# 10_Motor_Driver_2.net
KiCad netlist of a schematic drawn in Altium Designer
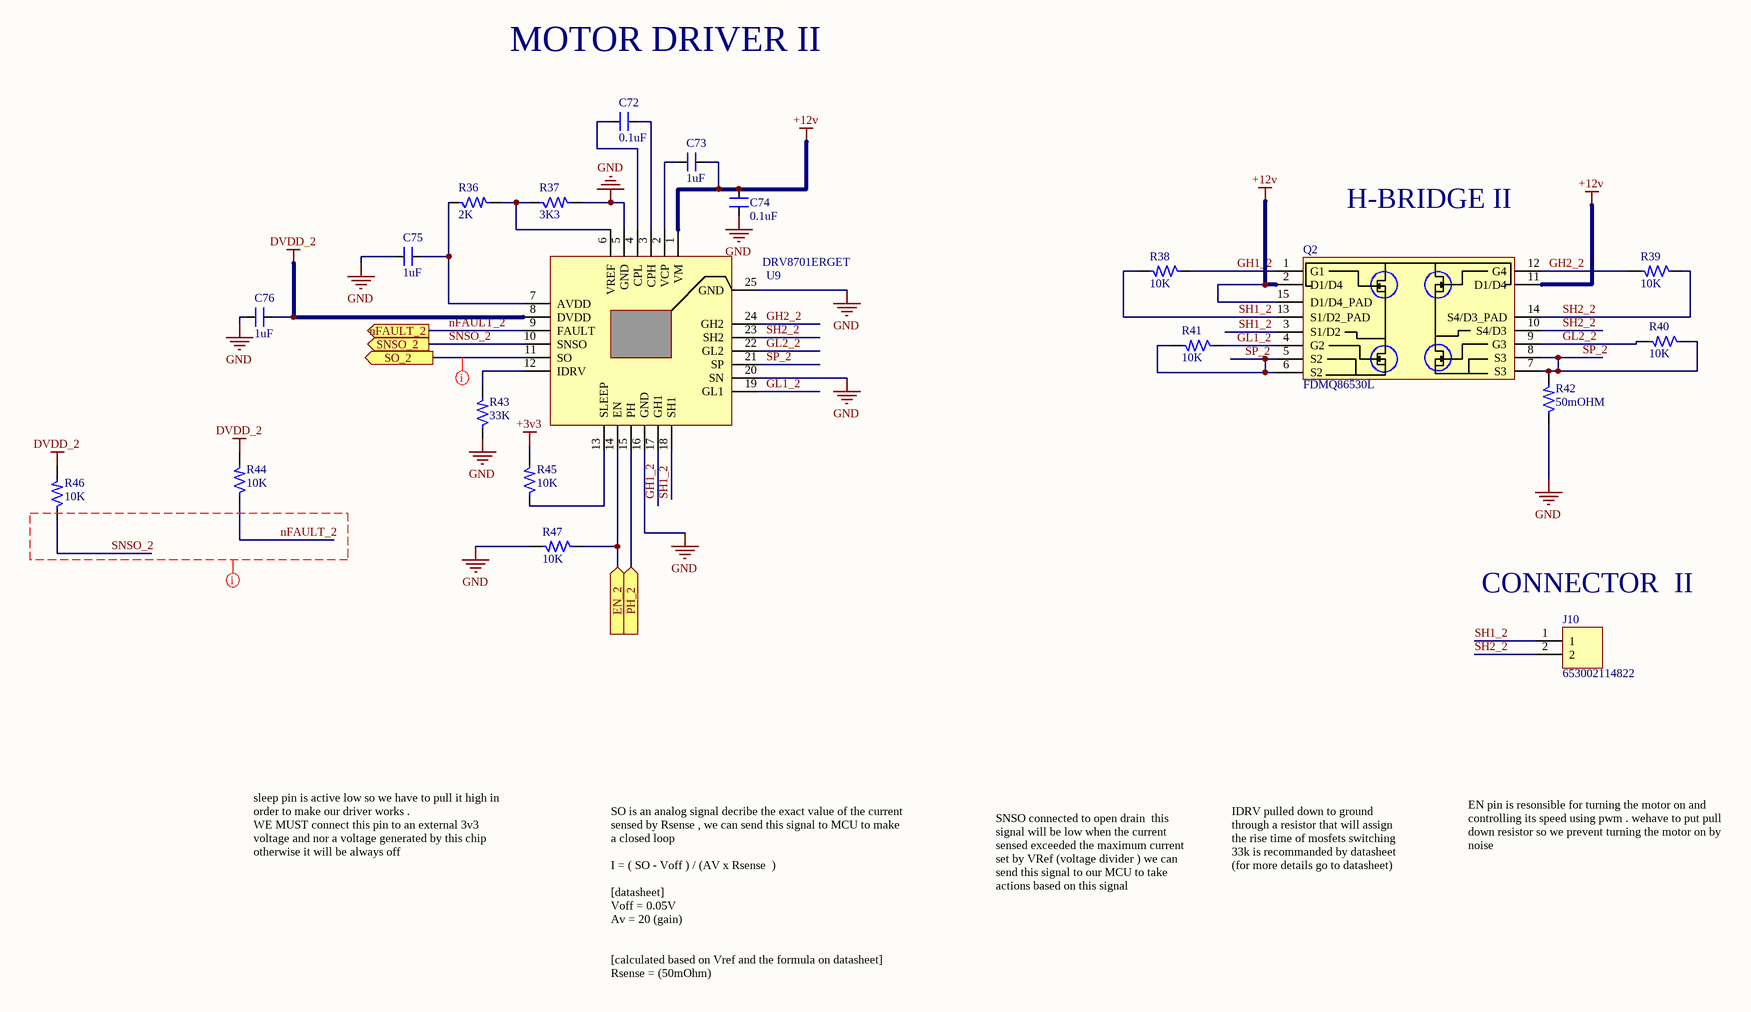
[diagram p0: [10]Motor_Driver_2.SchDoc]

(export (version "E")
  (design (tool "Eeschema 10.0.6"))
  (components
    (comp (ref "C72")
      (value "0.1uF")
      (footprint "CAP_0805")
      (description "0.1µF ±5% 50V Ceramic Capacitor X7R 0805 (2012 Metric)")
      (fields
        (field (name "MANUFACTURER") "AVX Corporation")
        (field (name "MANUFACTURER PART NUMBER") "08055C104JAT4A")
      )
      (libsource (lib "ESTEEMPCBLIB") (part "CAP_0.1uF-50V-5%-0805"))
    )
    (comp (ref "C73")
      (value "1uF")
      (footprint "CAP_0805")
      (description "1µF ±5% 50V Ceramic Capacitor X7R 0805 (2012 Metric)")
      (fields
        (field (name "MANUFACTURER") "Samsung")
        (field (name "MANUFACTURER PART NUMBER") "CC0805JKX7R9BB105")
      )
      (libsource (lib "ESTEEMPCBLIB") (part "CAP_1uF-50V-5%-0805"))
    )
    (comp (ref "C74")
      (value "0.1uF")
      (footprint "CAP_0805")
      (description "0.1µF ±5% 50V Ceramic Capacitor X7R 0805 (2012 Metric)")
      (fields
        (field (name "MANUFACTURER") "AVX Corporation")
        (field (name "MANUFACTURER PART NUMBER") "08055C104JAT4A")
      )
      (libsource (lib "ESTEEMPCBLIB") (part "CAP_0.1uF-50V-5%-0805"))
    )
    (comp (ref "C75")
      (value "1uF")
      (footprint "CAP_0805")
      (description "1µF ±5% 50V Ceramic Capacitor X7R 0805 (2012 Metric)")
      (fields
        (field (name "MANUFACTURER") "Samsung")
        (field (name "MANUFACTURER PART NUMBER") "CC0805JKX7R9BB105")
      )
      (libsource (lib "ESTEEMPCBLIB") (part "CAP_1uF-50V-5%-0805"))
    )
    (comp (ref "C76")
      (value "1uF")
      (footprint "CAP_0805")
      (description "1µF ±5% 50V Ceramic Capacitor X7R 0805 (2012 Metric)")
      (fields
        (field (name "MANUFACTURER") "Samsung")
        (field (name "MANUFACTURER PART NUMBER") "CC0805JKX7R9BB105")
      )
      (libsource (lib "ESTEEMPCBLIB") (part "CAP_1uF-50V-5%-0805"))
    )
    (comp (ref "J10")
      (value "653002114822")
      (footprint "CON2_50_653002114822_TH_ST")
      (description "2 Pins, 1 Row 1.25mm Pitch, Straight Connector, male")
      (fields (field (name "MANUFACTURER") "JST") (field (name "MATING PART NUMBER") "653002113322"))
      (libsource (lib "ESTEEMPCBLIB") (part "CON-PLG_2X1-50-ST-TH"))
    )
    (comp (ref "Q2")
      (value "FDMQ86530L")
      (footprint "DFN5045-12_33_212_27X15_SMD_1")
      (description "Mosfet Array 4 N-Channel 8A (Ta) Surface Mount V-DFN5045-12")
      (fields (field (name "MANUFACTURER") "ON Semiconductor"))
      (libsource (lib "ESTEEMPCBLIB") (part "MOSFET-N_60V-8A-V-DFN5045-12"))
    )
    (comp (ref "R36")
      (value "2K")
      (footprint "RES_0805")
      (description "2 kOhms ±1% 0.125W, 1/8W Chip Resistor 0805 (2012 Metric) Moisture Resistant Thick Film")
      (fields
        (field (name "MANUFACTURER") "TE Connectivity")
        (field (name "MANUFACTURER PART NUMBER") "RC0805FR-072KL")
      )
      (libsource (lib "ESTEEMPCBLIB") (part "RES_2K-0.125W-1%-0805"))
    )
    (comp (ref "R37")
      (value "3K3")
      (footprint "RES_0603")
      (description "3.3 kOhms ±1% 0.1W, 1/10W Chip Resistor 0603 (1608 Metric) Automotive AEC-Q200 Thick Film")
      (fields (field (name "MANUFACTURER") "Wilson") (field (name "MANUFACTURER PART NUMBER") "WR06X3301FTL"))
      (libsource (lib "ESTEEMPCBLIB") (part "RES_3.3K-0.1W-1%-0603"))
    )
    (comp (ref "R38")
      (value "10K")
      (footprint "RES_0805")
      (description "10 kOhms ±1% 0.125W, 1/8W Chip Resistor 0805 (2012 Metric) Automotive AEC-Q200 Thick Film")
      (fields (field (name "MANUFACTURER") "CTS") (field (name "MANUFACTURER PART NUMBER") "WR08X1002FTL"))
      (libsource (lib "ESTEEMPCBLIB") (part "RES_10K-0.125W-1%-0805"))
    )
    (comp (ref "R39")
      (value "10K")
      (footprint "RES_0805")
      (description "10 kOhms ±1% 0.125W, 1/8W Chip Resistor 0805 (2012 Metric) Automotive AEC-Q200 Thick Film")
      (fields (field (name "MANUFACTURER") "CTS") (field (name "MANUFACTURER PART NUMBER") "WR08X1002FTL"))
      (libsource (lib "ESTEEMPCBLIB") (part "RES_10K-0.125W-1%-0805"))
    )
    (comp (ref "R40")
      (value "10K")
      (footprint "RES_0805")
      (description "10 kOhms ±1% 0.125W, 1/8W Chip Resistor 0805 (2012 Metric) Automotive AEC-Q200 Thick Film")
      (fields (field (name "MANUFACTURER") "CTS") (field (name "MANUFACTURER PART NUMBER") "WR08X1002FTL"))
      (libsource (lib "ESTEEMPCBLIB") (part "RES_10K-0.125W-1%-0805"))
    )
    (comp (ref "R41")
      (value "10K")
      (footprint "RES_0805")
      (description "10 kOhms ±1% 0.125W, 1/8W Chip Resistor 0805 (2012 Metric) Automotive AEC-Q200 Thick Film")
      (fields (field (name "MANUFACTURER") "CTS") (field (name "MANUFACTURER PART NUMBER") "WR08X1002FTL"))
      (libsource (lib "ESTEEMPCBLIB") (part "RES_10K-0.125W-1%-0805"))
    )
    (comp (ref "R42")
      (value "50mOHM")
      (footprint "RES_2512")
      (fields
        (field (name "MANUFACTURER") "Yageo")
        (field (name "MANUFACTURER PART NUMBER") "PA2512FKF7W0R05E")
      )
      (libsource (lib "ESTEEMPCBLIB") (part "RES_50mOhm-2W-1%-2512"))
    )
    (comp (ref "R43")
      (value "33K")
      (footprint "RES_0805")
      (fields
        (field (name "MANUFACTURER") "Vishay BCcomponents")
        (field (name "MANUFACTURER PART NUMBER") "CRG0805F33K")
      )
      (libsource (lib "ESTEEMPCBLIB") (part "RES_33K-0.125W-1%-0805"))
    )
    (comp (ref "R44")
      (value "10K")
      (footprint "RES_0805")
      (description "10 kOhms ±1% 0.125W, 1/8W Chip Resistor 0805 (2012 Metric) Automotive AEC-Q200 Thick Film")
      (fields (field (name "MANUFACTURER") "CTS") (field (name "MANUFACTURER PART NUMBER") "WR08X1002FTL"))
      (libsource (lib "ESTEEMPCBLIB") (part "RES_10K-0.125W-1%-0805"))
    )
    (comp (ref "R45")
      (value "10K")
      (footprint "RES_0805")
      (description "10 kOhms ±1% 0.125W, 1/8W Chip Resistor 0805 (2012 Metric) Automotive AEC-Q200 Thick Film")
      (fields (field (name "MANUFACTURER") "CTS") (field (name "MANUFACTURER PART NUMBER") "WR08X1002FTL"))
      (libsource (lib "ESTEEMPCBLIB") (part "RES_10K-0.125W-1%-0805"))
    )
    (comp (ref "R46")
      (value "10K")
      (footprint "RES_0805")
      (description "10 kOhms ±1% 0.125W, 1/8W Chip Resistor 0805 (2012 Metric) Automotive AEC-Q200 Thick Film")
      (fields (field (name "MANUFACTURER") "CTS") (field (name "MANUFACTURER PART NUMBER") "WR08X1002FTL"))
      (libsource (lib "ESTEEMPCBLIB") (part "RES_10K-0.125W-1%-0805"))
    )
    (comp (ref "R47")
      (value "10K")
      (footprint "RES_0805")
      (description "10 kOhms ±1% 0.125W, 1/8W Chip Resistor 0805 (2012 Metric) Automotive AEC-Q200 Thick Film")
      (fields (field (name "MANUFACTURER") "CTS") (field (name "MANUFACTURER PART NUMBER") "WR08X1002FTL"))
      (libsource (lib "ESTEEMPCBLIB") (part "RES_10K-0.125W-1%-0805"))
    )
    (comp (ref "U9")
      (value "DRV8701ERGET")
      (footprint "VFQFN24_19.6_196_12X32_SMD_1")
      (description "Motor Driver Power MOSFET Parallel 24-VQFN (4x4)")
      (fields (field (name "MANUFACTURER") "Texas Instruments"))
      (libsource (lib "ESTEEMPCBLIB") (part "IC_DRV8701ERGET"))
    )
  )
  (nets
    (net (code "1") (name "+3v3") (class "Default")
      (node (ref "R45") (pin "2") (pinfunction "2_2") (pintype "passive"))
    )
    (net (code "2") (name "+12v") (class "Default")
      (node (ref "C73") (pin "2") (pinfunction "2_2") (pintype "passive"))
      (node (ref "C74") (pin "2") (pinfunction "2_2") (pintype "passive"))
      (node (ref "Q2") (pin "11") (pinfunction "D1/D4_11") (pintype "passive"))
      (node (ref "Q2") (pin "15") (pinfunction "D1/D4_PAD_15") (pintype "passive"))
      (node (ref "Q2") (pin "2") (pinfunction "D1/D4_2") (pintype "passive"))
      (node (ref "U9") (pin "1") (pinfunction "VM_1") (pintype "passive"))
    )
    (net (code "3") (name "/EN_2") (class "Default")
      (node (ref "R47") (pin "1") (pinfunction "1_1") (pintype "passive"))
      (node (ref "U9") (pin "14") (pinfunction "EN_14") (pintype "passive"))
    )
    (net (code "4") (name "/GH1_2") (class "Default")
      (node (ref "Q2") (pin "1") (pinfunction "G1_1") (pintype "passive"))
      (node (ref "R38") (pin "1") (pinfunction "1_1") (pintype "passive"))
      (node (ref "U9") (pin "17") (pinfunction "GH1_17") (pintype "passive"))
    )
    (net (code "5") (name "/GH2_2") (class "Default")
      (node (ref "Q2") (pin "12") (pinfunction "G4_12") (pintype "passive"))
      (node (ref "R39") (pin "2") (pinfunction "2_2") (pintype "passive"))
      (node (ref "U9") (pin "24") (pinfunction "GH2_24") (pintype "passive"))
    )
    (net (code "6") (name "/GL1_2") (class "Default")
      (node (ref "Q2") (pin "4") (pinfunction "G2_4") (pintype "passive"))
      (node (ref "R41") (pin "1") (pinfunction "1_1") (pintype "passive"))
      (node (ref "U9") (pin "19") (pinfunction "GL1_19") (pintype "passive"))
    )
    (net (code "7") (name "/GL2_2") (class "Default")
      (node (ref "Q2") (pin "9") (pinfunction "G3_9") (pintype "passive"))
      (node (ref "R40") (pin "2") (pinfunction "2_2") (pintype "passive"))
      (node (ref "U9") (pin "22") (pinfunction "GL2_22") (pintype "passive"))
    )
    (net (code "8") (name "/PH_2") (class "Default")
      (node (ref "U9") (pin "15") (pinfunction "PH_15") (pintype "passive"))
    )
    (net (code "9") (name "/SH1_2") (class "Default")
      (node (ref "J10") (pin "1") (pinfunction "1_1") (pintype "passive"))
      (node (ref "Q2") (pin "13") (pinfunction "S1/D2_PAD_13") (pintype "passive"))
      (node (ref "Q2") (pin "3") (pinfunction "S1/D2_3") (pintype "passive"))
      (node (ref "R38") (pin "2") (pinfunction "2_2") (pintype "passive"))
      (node (ref "U9") (pin "18") (pinfunction "SH1_18") (pintype "passive"))
    )
    (net (code "10") (name "/SH2_2") (class "Default")
      (node (ref "J10") (pin "2") (pinfunction "2_2") (pintype "passive"))
      (node (ref "Q2") (pin "10") (pinfunction "S4/D3_10") (pintype "passive"))
      (node (ref "Q2") (pin "14") (pinfunction "S4/D3_PAD_14") (pintype "passive"))
      (node (ref "R39") (pin "1") (pinfunction "1_1") (pintype "passive"))
      (node (ref "U9") (pin "23") (pinfunction "SH2_23") (pintype "passive"))
    )
    (net (code "11") (name "/SNSO_2") (class "Default")
      (node (ref "R46") (pin "1") (pinfunction "1_1") (pintype "passive"))
      (node (ref "U9") (pin "10") (pinfunction "SNSO_10") (pintype "passive"))
    )
    (net (code "12") (name "/SO_2") (class "Default")
      (node (ref "U9") (pin "11") (pinfunction "SO_11") (pintype "passive"))
    )
    (net (code "13") (name "/SP_2") (class "Default")
      (node (ref "Q2") (pin "5") (pinfunction "S2_5") (pintype "passive"))
      (node (ref "Q2") (pin "6") (pinfunction "S2_6") (pintype "passive"))
      (node (ref "Q2") (pin "7") (pinfunction "S3_7") (pintype "passive"))
      (node (ref "Q2") (pin "8") (pinfunction "S3_8") (pintype "passive"))
      (node (ref "R40") (pin "1") (pinfunction "1_1") (pintype "passive"))
      (node (ref "R41") (pin "2") (pinfunction "2_2") (pintype "passive"))
      (node (ref "R42") (pin "2") (pinfunction "2_2") (pintype "passive"))
      (node (ref "U9") (pin "21") (pinfunction "SP_21") (pintype "passive"))
    )
    (net (code "14") (name "/nFAULT_2") (class "Default")
      (node (ref "R44") (pin "1") (pinfunction "1_1") (pintype "passive"))
      (node (ref "U9") (pin "9") (pinfunction "FAULT_9") (pintype "passive"))
    )
    (net (code "15") (name "DVDD_2") (class "Default")
      (node (ref "C76") (pin "2") (pinfunction "2_2") (pintype "passive"))
      (node (ref "R44") (pin "2") (pinfunction "2_2") (pintype "passive"))
      (node (ref "R46") (pin "2") (pinfunction "2_2") (pintype "passive"))
      (node (ref "U9") (pin "8") (pinfunction "DVDD_8") (pintype "passive"))
    )
    (net (code "16") (name "GND") (class "Default")
      (node (ref "C74") (pin "1") (pinfunction "1_1") (pintype "passive"))
      (node (ref "C75") (pin "1") (pinfunction "1_1") (pintype "passive"))
      (node (ref "C76") (pin "1") (pinfunction "1_1") (pintype "passive"))
      (node (ref "R37") (pin "2") (pinfunction "2_2") (pintype "passive"))
      (node (ref "R42") (pin "1") (pinfunction "1_1") (pintype "passive"))
      (node (ref "R43") (pin "1") (pinfunction "1_1") (pintype "passive"))
      (node (ref "R47") (pin "2") (pinfunction "2_2") (pintype "passive"))
      (node (ref "U9") (pin "16") (pinfunction "GND_16") (pintype "passive"))
      (node (ref "U9") (pin "20") (pinfunction "SN_20") (pintype "passive"))
      (node (ref "U9") (pin "25") (pinfunction "GND_25") (pintype "passive"))
      (node (ref "U9") (pin "5") (pinfunction "GND_5") (pintype "passive"))
    )
    (net (code "17") (name "Net-(U9-AVDD)") (class "Default")
      (node (ref "C75") (pin "2") (pinfunction "2_2") (pintype "passive"))
      (node (ref "R36") (pin "1") (pinfunction "1_1") (pintype "passive"))
      (node (ref "U9") (pin "7") (pinfunction "AVDD_7") (pintype "passive"))
    )
    (net (code "18") (name "Net-(U9-CPH)") (class "Default")
      (node (ref "C72") (pin "2") (pinfunction "2_2") (pintype "passive"))
      (node (ref "U9") (pin "3") (pinfunction "CPH_3") (pintype "passive"))
    )
    (net (code "19") (name "Net-(U9-CPL)") (class "Default")
      (node (ref "C72") (pin "1") (pinfunction "1_1") (pintype "passive"))
      (node (ref "U9") (pin "4") (pinfunction "CPL_4") (pintype "passive"))
    )
    (net (code "20") (name "Net-(U9-IDRV)") (class "Default")
      (node (ref "R43") (pin "2") (pinfunction "2_2") (pintype "passive"))
      (node (ref "U9") (pin "12") (pinfunction "IDRV_12") (pintype "passive"))
    )
    (net (code "21") (name "Net-(U9-SLEEP)") (class "Default")
      (node (ref "R45") (pin "1") (pinfunction "1_1") (pintype "passive"))
      (node (ref "U9") (pin "13") (pinfunction "SLEEP_13") (pintype "passive"))
    )
    (net (code "22") (name "Net-(U9-VCP)") (class "Default")
      (node (ref "C73") (pin "1") (pinfunction "1_1") (pintype "passive"))
      (node (ref "U9") (pin "2") (pinfunction "VCP_2") (pintype "passive"))
    )
    (net (code "23") (name "Net-(U9-VREF)") (class "Default")
      (node (ref "R36") (pin "2") (pinfunction "2_2") (pintype "passive"))
      (node (ref "R37") (pin "1") (pinfunction "1_1") (pintype "passive"))
      (node (ref "U9") (pin "6") (pinfunction "VREF_6") (pintype "passive"))
    )
  )
)
